# touch-2ch-v3.net
KiCad netlist of a schematic drawn in Altium Designer
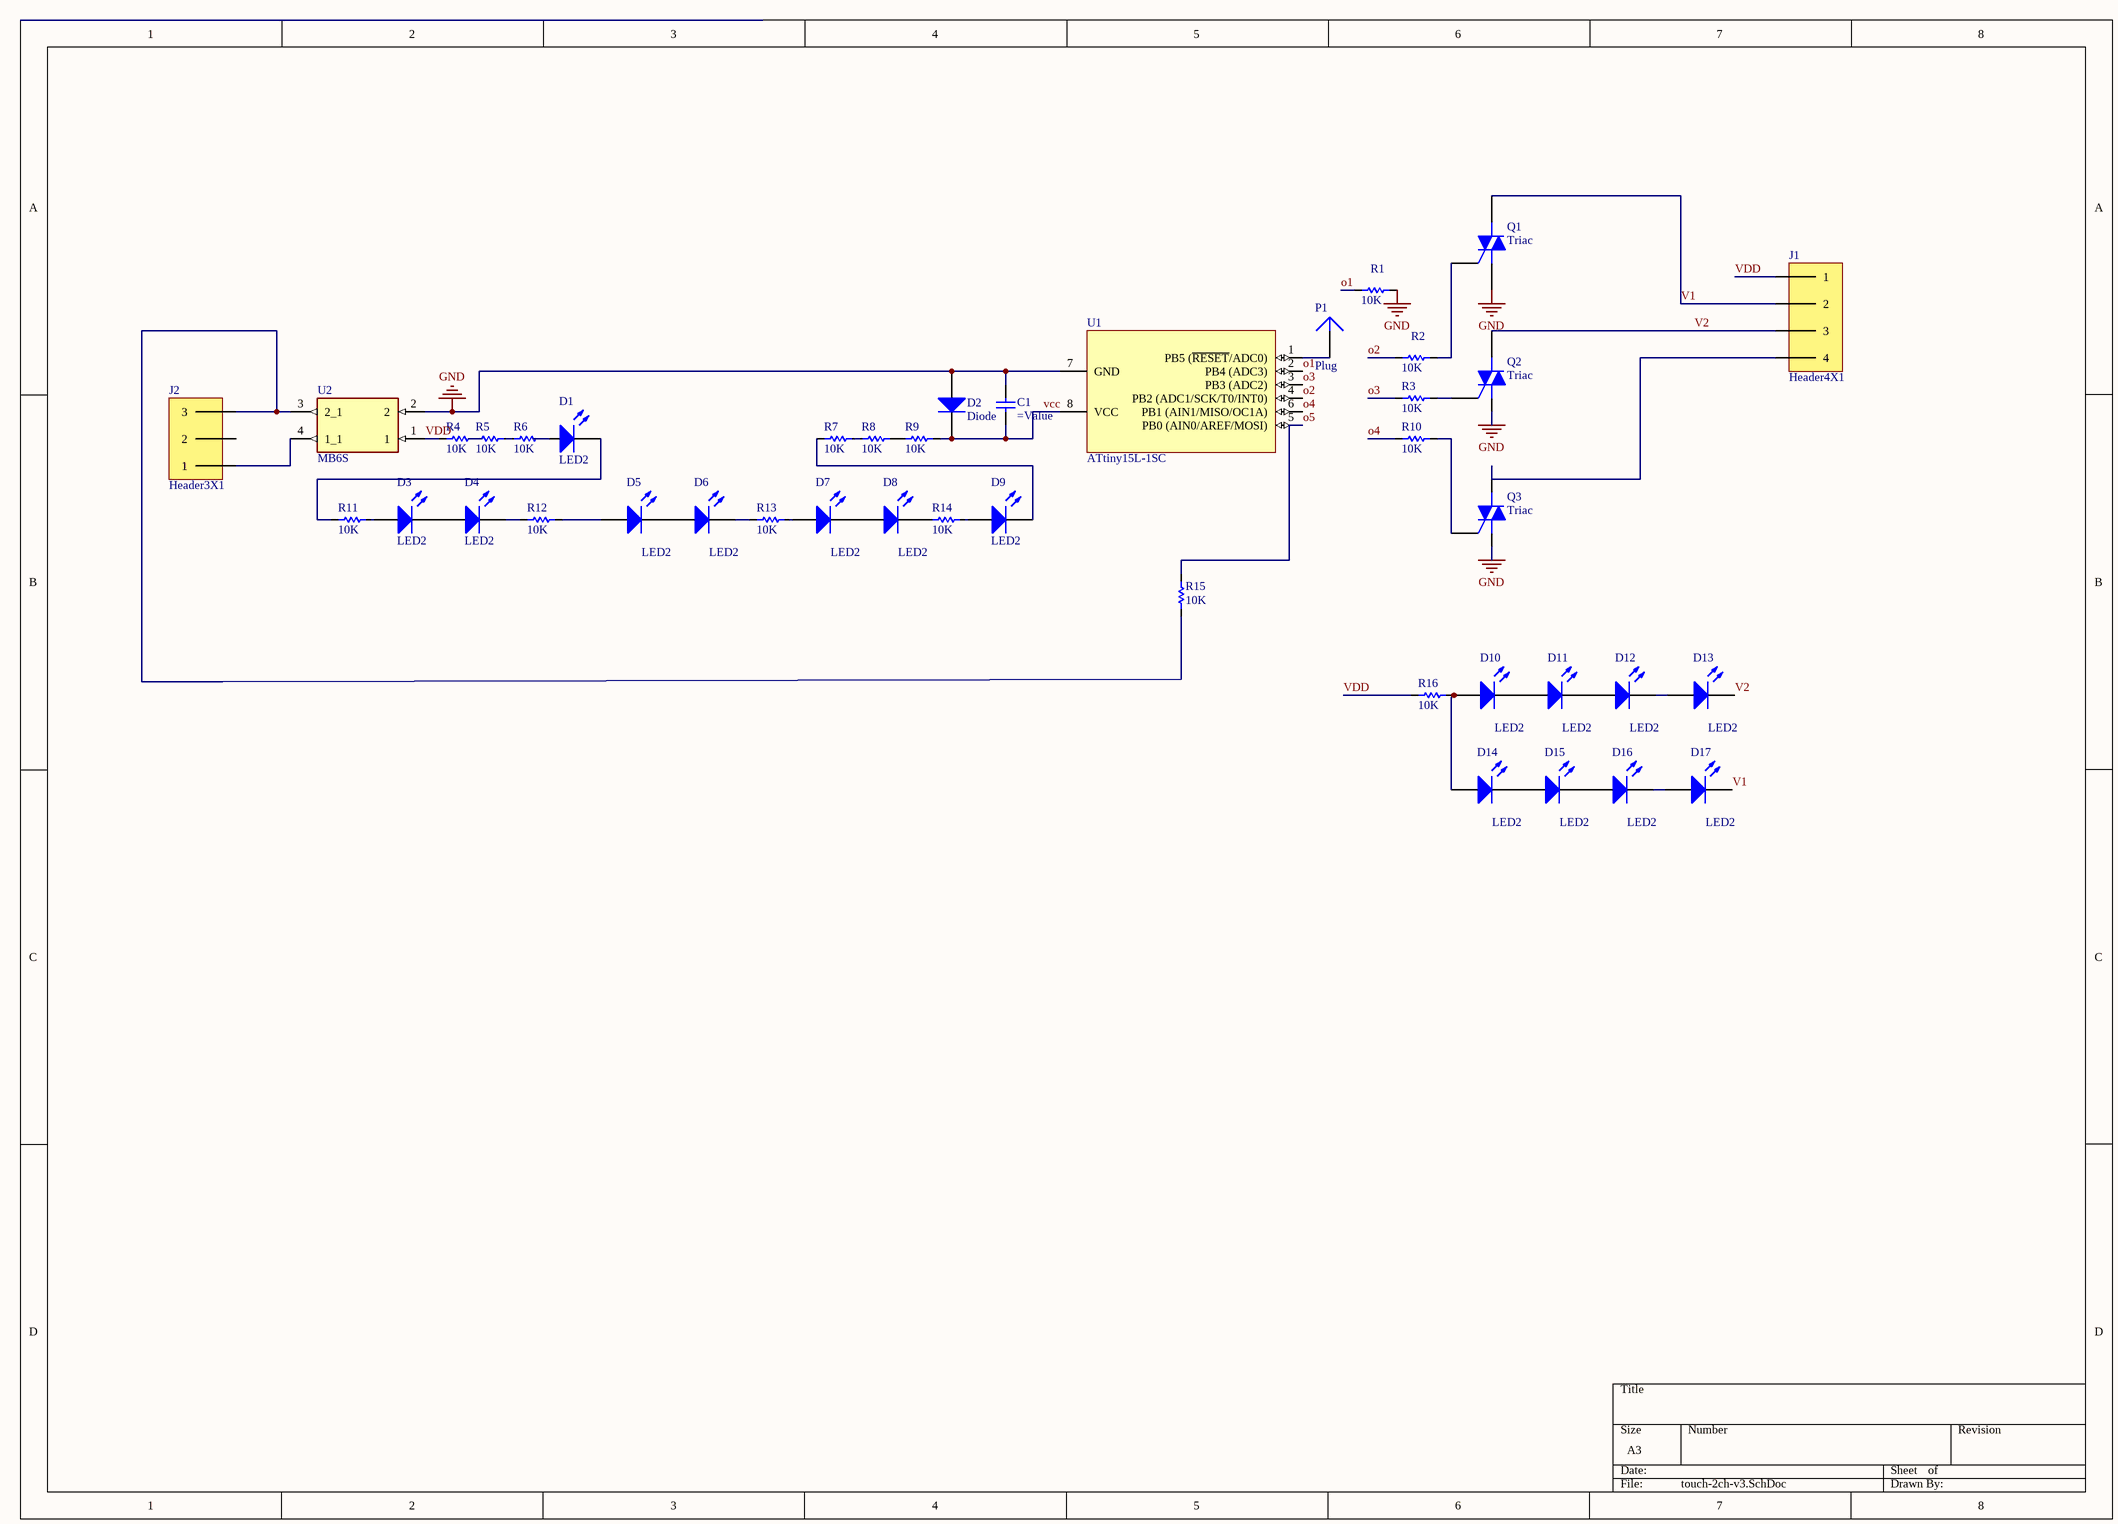
[diagram p0: touch-2ch-v3.SchDoc]

(export (version "E")
  (design (tool "Eeschema 10.0.6"))
  (components
    (comp (ref "C1")
      (value "~")
      (footprint "CAP 1206")
      (description "Capacitor")
      (libsource (lib "AltiumLib1") (part "Capacitor"))
    )
    (comp (ref "D1")
      (value "LED2")
      (footprint "3.2X1.6X1.1")
      (description "Typical RED, GREEN, YELLOW, AMBER GaAs LED")
      (fields (field (name "PUBLISHER") "Altium Limited"))
      (libsource (lib "Miscellaneous Devices") (part "LED2"))
    )
    (comp (ref "D2")
      (value "Diode")
      (footprint "C1206")
      (description "Default Diode")
      (fields (field (name "PUBLISHER") "Altium Limited"))
      (libsource (lib "Miscellaneous Devices") (part "Diode"))
    )
    (comp (ref "D3")
      (value "LED2")
      (footprint "3.2X1.6X1.1")
      (description "Typical RED, GREEN, YELLOW, AMBER GaAs LED")
      (fields (field (name "PUBLISHER") "Altium Limited"))
      (libsource (lib "Miscellaneous Devices") (part "LED2"))
    )
    (comp (ref "D4")
      (value "LED2")
      (footprint "3.2X1.6X1.1")
      (description "Typical RED, GREEN, YELLOW, AMBER GaAs LED")
      (fields (field (name "PUBLISHER") "Altium Limited"))
      (libsource (lib "Miscellaneous Devices") (part "LED2"))
    )
    (comp (ref "D5")
      (value "LED2")
      (footprint "3.2X1.6X1.1")
      (description "Typical RED, GREEN, YELLOW, AMBER GaAs LED")
      (fields (field (name "PUBLISHER") "Altium Limited"))
      (libsource (lib "Miscellaneous Devices") (part "LED2"))
    )
    (comp (ref "D6")
      (value "LED2")
      (footprint "3.2X1.6X1.1")
      (description "Typical RED, GREEN, YELLOW, AMBER GaAs LED")
      (fields (field (name "PUBLISHER") "Altium Limited"))
      (libsource (lib "Miscellaneous Devices") (part "LED2"))
    )
    (comp (ref "D7")
      (value "LED2")
      (footprint "3.2X1.6X1.1")
      (description "Typical RED, GREEN, YELLOW, AMBER GaAs LED")
      (fields (field (name "PUBLISHER") "Altium Limited"))
      (libsource (lib "Miscellaneous Devices") (part "LED2"))
    )
    (comp (ref "D8")
      (value "LED2")
      (footprint "3.2X1.6X1.1")
      (description "Typical RED, GREEN, YELLOW, AMBER GaAs LED")
      (fields (field (name "PUBLISHER") "Altium Limited"))
      (libsource (lib "Miscellaneous Devices") (part "LED2"))
    )
    (comp (ref "D9")
      (value "LED2")
      (footprint "3.2X1.6X1.1")
      (description "Typical RED, GREEN, YELLOW, AMBER GaAs LED")
      (fields (field (name "PUBLISHER") "Altium Limited"))
      (libsource (lib "Miscellaneous Devices") (part "LED2"))
    )
    (comp (ref "D10")
      (value "LED2")
      (footprint "3.2X1.6X1.1")
      (description "Typical RED, GREEN, YELLOW, AMBER GaAs LED")
      (fields (field (name "PUBLISHER") "Altium Limited"))
      (libsource (lib "Miscellaneous Devices") (part "LED2"))
    )
    (comp (ref "D11")
      (value "LED2")
      (footprint "3.2X1.6X1.1")
      (description "Typical RED, GREEN, YELLOW, AMBER GaAs LED")
      (fields (field (name "PUBLISHER") "Altium Limited"))
      (libsource (lib "Miscellaneous Devices") (part "LED2"))
    )
    (comp (ref "D12")
      (value "LED2")
      (footprint "3.2X1.6X1.1")
      (description "Typical RED, GREEN, YELLOW, AMBER GaAs LED")
      (fields (field (name "PUBLISHER") "Altium Limited"))
      (libsource (lib "Miscellaneous Devices") (part "LED2"))
    )
    (comp (ref "D13")
      (value "LED2")
      (footprint "3.2X1.6X1.1")
      (description "Typical RED, GREEN, YELLOW, AMBER GaAs LED")
      (fields (field (name "PUBLISHER") "Altium Limited"))
      (libsource (lib "Miscellaneous Devices") (part "LED2"))
    )
    (comp (ref "D14")
      (value "LED2")
      (footprint "3.2X1.6X1.1")
      (description "Typical RED, GREEN, YELLOW, AMBER GaAs LED")
      (fields (field (name "PUBLISHER") "Altium Limited"))
      (libsource (lib "Miscellaneous Devices") (part "LED2"))
    )
    (comp (ref "D15")
      (value "LED2")
      (footprint "3.2X1.6X1.1")
      (description "Typical RED, GREEN, YELLOW, AMBER GaAs LED")
      (fields (field (name "PUBLISHER") "Altium Limited"))
      (libsource (lib "Miscellaneous Devices") (part "LED2"))
    )
    (comp (ref "D16")
      (value "LED2")
      (footprint "3.2X1.6X1.1")
      (description "Typical RED, GREEN, YELLOW, AMBER GaAs LED")
      (fields (field (name "PUBLISHER") "Altium Limited"))
      (libsource (lib "Miscellaneous Devices") (part "LED2"))
    )
    (comp (ref "D17")
      (value "LED2")
      (footprint "3.2X1.6X1.1")
      (description "Typical RED, GREEN, YELLOW, AMBER GaAs LED")
      (fields (field (name "PUBLISHER") "Altium Limited"))
      (libsource (lib "Miscellaneous Devices") (part "LED2"))
    )
    (comp (ref "J1")
      (value "Header4X1")
      (footprint "HEADER 4X1")
      (libsource (lib "AltiumLib1") (part "Header4X1"))
    )
    (comp (ref "J2")
      (value "Header3X1")
      (footprint "HEADER 3X1")
      (libsource (lib "AltiumLib1") (part "Header3X1"))
    )
    (comp (ref "P1")
      (value "Plug")
      (footprint "PIN1")
      (fields (field (name "PUBLISHER") "Altium Limited"))
      (libsource (lib "Miscellaneous Connectors") (part "Plug"))
    )
    (comp (ref "Q1")
      (value "Triac")
      (footprint "SOT89N")
      (description "Silicon Bidirectional Triode Thyristor")
      (fields (field (name "PUBLISHER") "Altium Limited"))
      (libsource (lib "Miscellaneous Devices") (part "Triac"))
    )
    (comp (ref "Q2")
      (value "Triac")
      (footprint "SOT89N")
      (description "Silicon Bidirectional Triode Thyristor")
      (fields (field (name "PUBLISHER") "Altium Limited"))
      (libsource (lib "Miscellaneous Devices") (part "Triac"))
    )
    (comp (ref "Q3")
      (value "Triac")
      (footprint "SOT89N")
      (description "Silicon Bidirectional Triode Thyristor")
      (fields (field (name "PUBLISHER") "Altium Limited"))
      (libsource (lib "Miscellaneous Devices") (part "Triac"))
    )
    (comp (ref "R1")
      (value "10K")
      (footprint "RES 1206 (3216X08L)")
      (description "Resistor")
      (fields (field (name "TOLERANCE") "5%") (field (name "POWER") "1/4 W"))
      (libsource (lib "AltiumLib1") (part "Resistor"))
    )
    (comp (ref "R2")
      (value "10K")
      (footprint "RES 1206 (3216X08L)")
      (description "Resistor")
      (fields (field (name "TOLERANCE") "5%") (field (name "POWER") "1/4 W"))
      (libsource (lib "AltiumLib1") (part "Resistor"))
    )
    (comp (ref "R3")
      (value "10K")
      (footprint "RES 1206 (3216X08L)")
      (description "Resistor")
      (fields (field (name "TOLERANCE") "5%") (field (name "POWER") "1/4 W"))
      (libsource (lib "AltiumLib1") (part "Resistor"))
    )
    (comp (ref "R4")
      (value "10K")
      (footprint "RES 2010 (5026X08L)")
      (description "Resistor")
      (fields (field (name "TOLERANCE") "5%") (field (name "POWER") "1/4 W"))
      (libsource (lib "AltiumLib1") (part "Resistor"))
    )
    (comp (ref "R5")
      (value "10K")
      (footprint "RES 2010 (5026X08L)")
      (description "Resistor")
      (fields (field (name "TOLERANCE") "5%") (field (name "POWER") "1/4 W"))
      (libsource (lib "AltiumLib1") (part "Resistor"))
    )
    (comp (ref "R6")
      (value "10K")
      (footprint "RES 2010 (5026X08L)")
      (description "Resistor")
      (fields (field (name "TOLERANCE") "5%") (field (name "POWER") "1/4 W"))
      (libsource (lib "AltiumLib1") (part "Resistor"))
    )
    (comp (ref "R7")
      (value "10K")
      (footprint "RES 2010 (5026X08L)")
      (description "Resistor")
      (fields (field (name "TOLERANCE") "5%") (field (name "POWER") "1/4 W"))
      (libsource (lib "AltiumLib1") (part "Resistor"))
    )
    (comp (ref "R8")
      (value "10K")
      (footprint "RES 2010 (5026X08L)")
      (description "Resistor")
      (fields (field (name "TOLERANCE") "5%") (field (name "POWER") "1/4 W"))
      (libsource (lib "AltiumLib1") (part "Resistor"))
    )
    (comp (ref "R9")
      (value "10K")
      (footprint "RES 2010 (5026X08L)")
      (description "Resistor")
      (fields (field (name "TOLERANCE") "5%") (field (name "POWER") "1/4 W"))
      (libsource (lib "AltiumLib1") (part "Resistor"))
    )
    (comp (ref "R10")
      (value "10K")
      (footprint "RES 1206 (3216X08L)")
      (description "Resistor")
      (fields (field (name "TOLERANCE") "5%") (field (name "POWER") "1/4 W"))
      (libsource (lib "AltiumLib1") (part "Resistor"))
    )
    (comp (ref "R11")
      (value "10K")
      (footprint "RES 2010 (5026X08L)")
      (description "Resistor")
      (fields (field (name "TOLERANCE") "5%") (field (name "POWER") "1/4 W"))
      (libsource (lib "AltiumLib1") (part "Resistor"))
    )
    (comp (ref "R12")
      (value "10K")
      (footprint "RES 2010 (5026X08L)")
      (description "Resistor")
      (fields (field (name "TOLERANCE") "5%") (field (name "POWER") "1/4 W"))
      (libsource (lib "AltiumLib1") (part "Resistor"))
    )
    (comp (ref "R13")
      (value "10K")
      (footprint "RES 2010 (5026X08L)")
      (description "Resistor")
      (fields (field (name "TOLERANCE") "5%") (field (name "POWER") "1/4 W"))
      (libsource (lib "AltiumLib1") (part "Resistor"))
    )
    (comp (ref "R14")
      (value "10K")
      (footprint "RES 2010 (5026X08L)")
      (description "Resistor")
      (fields (field (name "TOLERANCE") "5%") (field (name "POWER") "1/4 W"))
      (libsource (lib "AltiumLib1") (part "Resistor"))
    )
    (comp (ref "R15")
      (value "10K")
      (footprint "RES 1206 (3216X08L)")
      (description "Resistor")
      (fields (field (name "TOLERANCE") "5%") (field (name "POWER") "1/4 W"))
      (libsource (lib "AltiumLib1") (part "Resistor"))
    )
    (comp (ref "R16")
      (value "10K")
      (footprint "RES 2010 (5026X08L)")
      (description "Resistor")
      (fields (field (name "TOLERANCE") "5%") (field (name "POWER") "1/4 W"))
      (libsource (lib "AltiumLib1") (part "Resistor"))
    )
    (comp (ref "U1")
      (value "ATtiny15L-1SC")
      (footprint "8S2_N")
      (description "8-Bit AVR Microcontroller with 1K Byte of Flash Memory")
      (fields (field (name "PUBLISHER") "Altium Limited"))
      (libsource (lib "Atmel Microcontroller 8-Bit AVR") (part "ATtiny15L-1SC"))
    )
    (comp (ref "U2")
      (value "MB6S")
      (footprint "SOIC245P670X270-4N")
      (description "Bridge Rectifier Single Phase Standard 600V Surface Mount 4-SOIC")
      (fields (field (name "MF") "ON Semiconductor") (field (name "DIGI-KEY_PART_NUMBER") "MB6SCT-ND"))
      (libsource (lib "MB6S") (part "MB6S"))
    )
  )
  (nets
    (net (code "1") (name "/V1") (class "Default")
      (node (ref "D17") (pin "2") (pinfunction "K_2") (pintype "passive"))
      (node (ref "J1") (pin "2") (pinfunction "2_2") (pintype "passive"))
      (node (ref "Q1") (pin "2") (pinfunction "M2_2") (pintype "passive"))
    )
    (net (code "2") (name "/V2") (class "Default")
      (node (ref "D13") (pin "2") (pinfunction "K_2") (pintype "passive"))
      (node (ref "J1") (pin "3") (pinfunction "3_3") (pintype "passive"))
      (node (ref "Q2") (pin "2") (pinfunction "M2_2") (pintype "passive"))
    )
    (net (code "3") (name "/VDD") (class "Default")
      (node (ref "J1") (pin "1") (pinfunction "1_1") (pintype "passive"))
      (node (ref "R16") (pin "1") (pinfunction "1_1") (pintype "passive"))
      (node (ref "R4") (pin "1") (pinfunction "1_1") (pintype "passive"))
      (node (ref "U2") (pin "1") (pinfunction "1_1") (pintype "input"))
    )
    (net (code "4") (name "/o1") (class "Default")
      (node (ref "R1") (pin "1") (pinfunction "1_1") (pintype "passive"))
      (node (ref "U1") (pin "2") (pinfunction "PB4_(ADC3)_2") (pintype "bidirectional"))
    )
    (net (code "5") (name "/o2") (class "Default")
      (node (ref "R2") (pin "1") (pinfunction "1_1") (pintype "passive"))
      (node (ref "U1") (pin "4") (pinfunction "PB2_(ADC1/SCK/T0/INT0)_4") (pintype "bidirectional"))
    )
    (net (code "6") (name "/o3") (class "Default")
      (node (ref "R3") (pin "1") (pinfunction "1_1") (pintype "passive"))
      (node (ref "U1") (pin "3") (pinfunction "PB3_(ADC2)_3") (pintype "bidirectional"))
    )
    (net (code "7") (name "/o4") (class "Default")
      (node (ref "R10") (pin "1") (pinfunction "1_1") (pintype "passive"))
      (node (ref "U1") (pin "6") (pinfunction "PB1_(AIN1/MISO/OC1A)_6") (pintype "bidirectional"))
    )
    (net (code "8") (name "/o5") (class "Default")
      (node (ref "R15") (pin "2") (pinfunction "2_2") (pintype "passive"))
      (node (ref "U1") (pin "5") (pinfunction "PB0_(AIN0/AREF/MOSI)_5") (pintype "bidirectional"))
    )
    (net (code "9") (name "/vcc") (class "Default")
      (node (ref "C1") (pin "1") (pinfunction "+_1") (pintype "passive"))
      (node (ref "D2") (pin "2") (pinfunction "K_2") (pintype "passive"))
      (node (ref "R9") (pin "2") (pinfunction "2_2") (pintype "passive"))
      (node (ref "U1") (pin "8") (pinfunction "VCC_8") (pintype "power_in"))
    )
    (net (code "10") (name "GND") (class "Default")
      (node (ref "C1") (pin "2") (pinfunction "-_2") (pintype "passive"))
      (node (ref "D2") (pin "1") (pinfunction "A_1") (pintype "passive"))
      (node (ref "Q1") (pin "1") (pinfunction "M1_1") (pintype "passive"))
      (node (ref "Q2") (pin "1") (pinfunction "M1_1") (pintype "passive"))
      (node (ref "Q3") (pin "1") (pinfunction "M1_1") (pintype "passive"))
      (node (ref "R1") (pin "2") (pinfunction "2_2") (pintype "passive"))
      (node (ref "U1") (pin "7") (pinfunction "GND_7") (pintype "power_in"))
      (node (ref "U2") (pin "2") (pinfunction "2_2") (pintype "input"))
    )
    (net (code "11") (name "Net-(D1-A)") (class "Default")
      (node (ref "D1") (pin "1") (pinfunction "A_1") (pintype "passive"))
      (node (ref "R6") (pin "2") (pinfunction "2_2") (pintype "passive"))
    )
    (net (code "12") (name "Net-(D1-K)") (class "Default")
      (node (ref "D1") (pin "2") (pinfunction "K_2") (pintype "passive"))
      (node (ref "R11") (pin "1") (pinfunction "1_1") (pintype "passive"))
    )
    (net (code "13") (name "Net-(D3-A)") (class "Default")
      (node (ref "D3") (pin "1") (pinfunction "A_1") (pintype "passive"))
      (node (ref "R11") (pin "2") (pinfunction "2_2") (pintype "passive"))
    )
    (net (code "14") (name "Net-(D3-K)") (class "Default")
      (node (ref "D3") (pin "2") (pinfunction "K_2") (pintype "passive"))
      (node (ref "D4") (pin "1") (pinfunction "A_1") (pintype "passive"))
    )
    (net (code "15") (name "Net-(D4-K)") (class "Default")
      (node (ref "D4") (pin "2") (pinfunction "K_2") (pintype "passive"))
      (node (ref "R12") (pin "1") (pinfunction "1_1") (pintype "passive"))
    )
    (net (code "16") (name "Net-(D5-A)") (class "Default")
      (node (ref "D5") (pin "1") (pinfunction "A_1") (pintype "passive"))
      (node (ref "R12") (pin "2") (pinfunction "2_2") (pintype "passive"))
    )
    (net (code "17") (name "Net-(D5-K)") (class "Default")
      (node (ref "D5") (pin "2") (pinfunction "K_2") (pintype "passive"))
      (node (ref "D6") (pin "1") (pinfunction "A_1") (pintype "passive"))
    )
    (net (code "18") (name "Net-(D6-K)") (class "Default")
      (node (ref "D6") (pin "2") (pinfunction "K_2") (pintype "passive"))
      (node (ref "R13") (pin "1") (pinfunction "1_1") (pintype "passive"))
    )
    (net (code "19") (name "Net-(D7-A)") (class "Default")
      (node (ref "D7") (pin "1") (pinfunction "A_1") (pintype "passive"))
      (node (ref "R13") (pin "2") (pinfunction "2_2") (pintype "passive"))
    )
    (net (code "20") (name "Net-(D7-K)") (class "Default")
      (node (ref "D7") (pin "2") (pinfunction "K_2") (pintype "passive"))
      (node (ref "D8") (pin "1") (pinfunction "A_1") (pintype "passive"))
    )
    (net (code "21") (name "Net-(D8-K)") (class "Default")
      (node (ref "D8") (pin "2") (pinfunction "K_2") (pintype "passive"))
      (node (ref "R14") (pin "1") (pinfunction "1_1") (pintype "passive"))
    )
    (net (code "22") (name "Net-(D9-A)") (class "Default")
      (node (ref "D9") (pin "1") (pinfunction "A_1") (pintype "passive"))
      (node (ref "R14") (pin "2") (pinfunction "2_2") (pintype "passive"))
    )
    (net (code "23") (name "Net-(D9-K)") (class "Default")
      (node (ref "D9") (pin "2") (pinfunction "K_2") (pintype "passive"))
      (node (ref "R7") (pin "1") (pinfunction "1_1") (pintype "passive"))
    )
    (net (code "24") (name "Net-(D10-A)") (class "Default")
      (node (ref "D10") (pin "1") (pinfunction "A_1") (pintype "passive"))
      (node (ref "D14") (pin "1") (pinfunction "A_1") (pintype "passive"))
      (node (ref "R16") (pin "2") (pinfunction "2_2") (pintype "passive"))
    )
    (net (code "25") (name "Net-(D10-K)") (class "Default")
      (node (ref "D10") (pin "2") (pinfunction "K_2") (pintype "passive"))
      (node (ref "D11") (pin "1") (pinfunction "A_1") (pintype "passive"))
    )
    (net (code "26") (name "Net-(D11-K)") (class "Default")
      (node (ref "D11") (pin "2") (pinfunction "K_2") (pintype "passive"))
      (node (ref "D12") (pin "1") (pinfunction "A_1") (pintype "passive"))
    )
    (net (code "27") (name "Net-(D12-K)") (class "Default")
      (node (ref "D12") (pin "2") (pinfunction "K_2") (pintype "passive"))
      (node (ref "D13") (pin "1") (pinfunction "A_1") (pintype "passive"))
    )
    (net (code "28") (name "Net-(D14-K)") (class "Default")
      (node (ref "D14") (pin "2") (pinfunction "K_2") (pintype "passive"))
      (node (ref "D15") (pin "1") (pinfunction "A_1") (pintype "passive"))
    )
    (net (code "29") (name "Net-(D15-K)") (class "Default")
      (node (ref "D15") (pin "2") (pinfunction "K_2") (pintype "passive"))
      (node (ref "D16") (pin "1") (pinfunction "A_1") (pintype "passive"))
    )
    (net (code "30") (name "Net-(D16-K)") (class "Default")
      (node (ref "D16") (pin "2") (pinfunction "K_2") (pintype "passive"))
      (node (ref "D17") (pin "1") (pinfunction "A_1") (pintype "passive"))
    )
    (net (code "31") (name "Net-(Q1-G)") (class "Default")
      (node (ref "Q1") (pin "3") (pinfunction "G_3") (pintype "passive"))
      (node (ref "R2") (pin "2") (pinfunction "2_2") (pintype "passive"))
    )
    (net (code "32") (name "Net-(Q2-G)") (class "Default")
      (node (ref "Q2") (pin "3") (pinfunction "G_3") (pintype "passive"))
      (node (ref "R3") (pin "2") (pinfunction "2_2") (pintype "passive"))
    )
    (net (code "33") (name "Net-(Q3-G)") (class "Default")
      (node (ref "Q3") (pin "3") (pinfunction "G_3") (pintype "passive"))
      (node (ref "R10") (pin "2") (pinfunction "2_2") (pintype "passive"))
    )
    (net (code "34") (name "Net-(Q3-M2)") (class "Default")
      (node (ref "J1") (pin "4") (pinfunction "4_4") (pintype "passive"))
      (node (ref "Q3") (pin "2") (pinfunction "M2_2") (pintype "passive"))
    )
    (net (code "35") (name "Net-(R4-Pad2)") (class "Default")
      (node (ref "R4") (pin "2") (pinfunction "2_2") (pintype "passive"))
      (node (ref "R5") (pin "1") (pinfunction "1_1") (pintype "passive"))
    )
    (net (code "36") (name "Net-(R5-Pad2)") (class "Default")
      (node (ref "R5") (pin "2") (pinfunction "2_2") (pintype "passive"))
      (node (ref "R6") (pin "1") (pinfunction "1_1") (pintype "passive"))
    )
    (net (code "37") (name "Net-(R7-Pad2)") (class "Default")
      (node (ref "R7") (pin "2") (pinfunction "2_2") (pintype "passive"))
      (node (ref "R8") (pin "1") (pinfunction "1_1") (pintype "passive"))
    )
    (net (code "38") (name "Net-(R8-Pad2)") (class "Default")
      (node (ref "R8") (pin "2") (pinfunction "2_2") (pintype "passive"))
      (node (ref "R9") (pin "1") (pinfunction "1_1") (pintype "passive"))
    )
    (net (code "39") (name "Net-(U1-PB5_(~{RESET}{slash}ADC0))") (class "Default")
      (node (ref "P1") (pin "1") (pinfunction "1_1") (pintype "passive"))
      (node (ref "U1") (pin "1") (pinfunction "PB5_(~{RESET}/ADC0)_1") (pintype "bidirectional"))
    )
    (net (code "40") (name "Net-(U2-1_1)") (class "Default")
      (node (ref "J2") (pin "1") (pinfunction "1_1") (pintype "passive"))
      (node (ref "U2") (pin "4") (pinfunction "1_1_4") (pintype "output"))
    )
    (net (code "41") (name "Net-(U2-2_1)") (class "Default")
      (node (ref "J2") (pin "3") (pinfunction "3_3") (pintype "passive"))
      (node (ref "R15") (pin "1") (pinfunction "1_1") (pintype "passive"))
      (node (ref "U2") (pin "3") (pinfunction "2_1_3") (pintype "output"))
    )
    (net (code "42") (name "unconnected-(J2-Pad2)") (class "Default")
      (node (ref "J2") (pin "2") (pinfunction "2_2") (pintype "passive"))
    )
  )
)
